# POW.net
KiCad netlist of a schematic drawn in Altium Designer
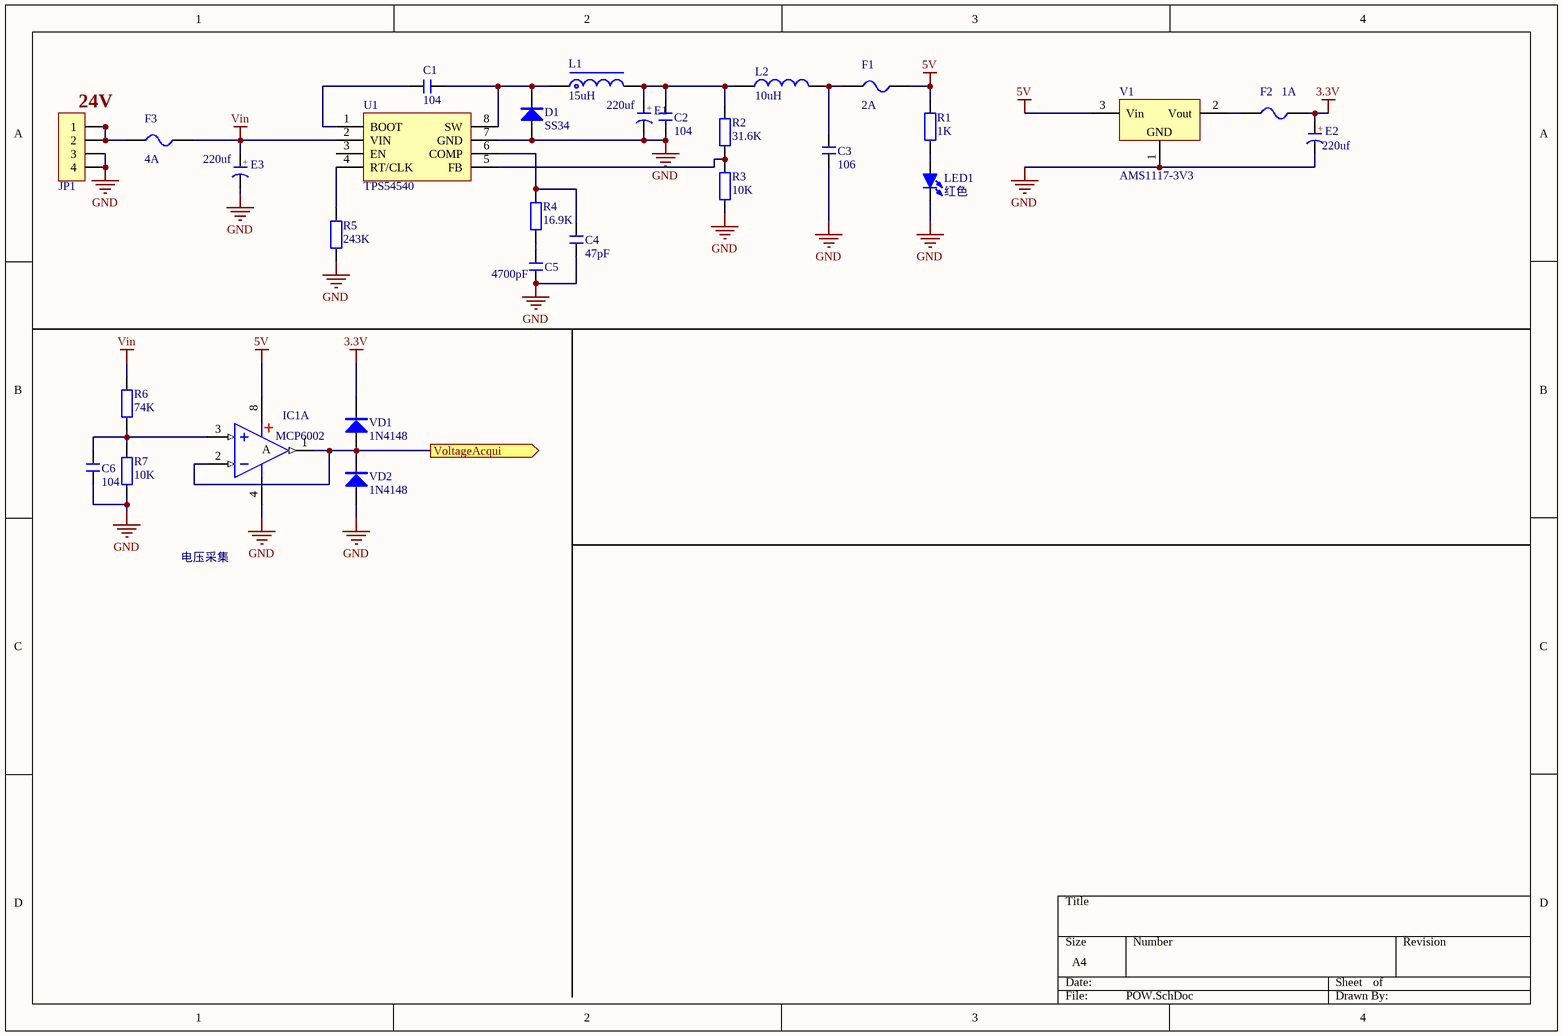
[diagram p0: POW.SchDoc]

(export (version "E")
  (design (tool "Eeschema 10.0.6"))
  (components
    (comp (ref "C1")
      (value "104")
      (footprint "C 0603_L")
      (description "无极性贴片电容")
      (fields (field (name "版权归属") "源创客"))
      (libsource (lib "3.1   - 电阻-电容-电感") (part "C"))
    )
    (comp (ref "C2")
      (value "104")
      (footprint "C 0603_L")
      (description "无极性贴片电容")
      (fields (field (name "版权归属") "源创客"))
      (libsource (lib "3.1   - 电阻-电容-电感") (part "C"))
    )
    (comp (ref "C3")
      (value "106")
      (footprint "C 0603_L")
      (description "无极性贴片电容")
      (fields (field (name "版权归属") "源创客"))
      (libsource (lib "3.1   - 电阻-电容-电感") (part "C"))
    )
    (comp (ref "C4")
      (value "47pF")
      (footprint "C 0603_L")
      (description "无极性贴片电容")
      (fields (field (name "版权归属") "源创客"))
      (libsource (lib "3.1   - 电阻-电容-电感") (part "C"))
    )
    (comp (ref "C5")
      (value "4700pF")
      (footprint "C 0603_L")
      (description "无极性贴片电容")
      (fields (field (name "版权归属") "源创客"))
      (libsource (lib "3.1   - 电阻-电容-电感") (part "C"))
    )
    (comp (ref "C6")
      (value "104")
      (footprint "C 0603_m")
      (description "无极性贴片电容")
      (fields (field (name "版权归属") "源创客"))
      (libsource (lib "电阻-电容-电感") (part "C"))
    )
    (comp (ref "D1")
      (value "SS34")
      (footprint "SMC")
      (description "肖特基二极管")
      (fields (field (name "版权归属") "源创客"))
      (libsource (lib "8.1   - 二极管-整流桥") (part "SS34"))
    )
    (comp (ref "E1")
      (value "220uf")
      (footprint "CM E(8*10.2)")
      (description "贴片电解电容")
      (fields (field (name "版权归属") "源创客"))
      (libsource (lib "电阻-电容-电感") (part "C-CM"))
    )
    (comp (ref "E2")
      (value "220uf")
      (footprint "CM E(8*10.2)")
      (description "贴片电解电容")
      (fields (field (name "版权归属") "源创客"))
      (libsource (lib "电阻-电容-电感") (part "C-CM"))
    )
    (comp (ref "E3")
      (value "220uf")
      (footprint "CM E(8*10.2)")
      (description "贴片电解电容")
      (fields (field (name "版权归属") "源创客"))
      (libsource (lib "电阻-电容-电感") (part "C-CM"))
    )
    (comp (ref "F1")
      (value "2A")
      (footprint "FU 1206")
      (description "贴片保险丝")
      (fields (field (name "版权归属") "源创客"))
      (libsource (lib "保险丝-晶振") (part "FU"))
    )
    (comp (ref "F2")
      (value "1A")
      (footprint "FU 0805")
      (description "贴片保险丝")
      (fields (field (name "版权归属") "源创客"))
      (libsource (lib "保险丝-晶振") (part "FU"))
    )
    (comp (ref "F3")
      (value "4A")
      (footprint "FU 1206")
      (description "贴片保险丝")
      (fields (field (name "版权归属") "源创客"))
      (libsource (lib "保险丝-晶振") (part "FU"))
    )
    (comp (ref "IC1")
      (value "MCP6002")
      (footprint "SOP8_N")
      (description "双路运放")
      (fields (field (name "版权归属") "源创客"))
      (libsource (lib "IC芯片") (part "LM358"))
    )
    (comp (ref "JP1")
      (value "HDR-1X4")
      (footprint "XH2.54-LI-4P")
      (description "4P接插件")
      (fields (field (name "版权归属") "源创客"))
      (libsource (lib "4.5   - 接插件-脚距2.54") (part "Header 4"))
    )
    (comp (ref "L1")
      (value "15uH")
      (footprint "CDRH73")
      (description "功率屏蔽电感")
      (fields (field (name "版权归属") "源创客"))
      (libsource (lib "电阻-电容-电感") (part "L-CDRH"))
    )
    (comp (ref "L2")
      (value "10uH")
      (footprint "L 0805")
      (description "小功率贴片电感")
      (fields (field (name "版权归属") "源创客"))
      (libsource (lib "电阻-电容-电感") (part "L"))
    )
    (comp (ref "LED1")
      (value "红色")
      (footprint "LED 0603G")
      (description "贴片LED")
      (fields (field (name "版权归属") "源创客"))
      (libsource (lib "LED") (part "LED-SMD"))
    )
    (comp (ref "R1")
      (value "1K")
      (footprint "R 0603_L")
      (description "贴片电阻")
      (fields (field (name "版权归属") "源创客"))
      (libsource (lib "3.1   - 电阻-电容-电感") (part "R"))
    )
    (comp (ref "R2")
      (value "31.6K")
      (footprint "R 0603_L")
      (description "贴片电阻")
      (fields (field (name "版权归属") "源创客"))
      (libsource (lib "3.1   - 电阻-电容-电感") (part "R"))
    )
    (comp (ref "R3")
      (value "10K")
      (footprint "R 0603_L")
      (description "贴片电阻")
      (fields (field (name "版权归属") "源创客"))
      (libsource (lib "3.1   - 电阻-电容-电感") (part "R"))
    )
    (comp (ref "R4")
      (value "16.9K")
      (footprint "R 0603_L")
      (description "贴片电阻")
      (fields (field (name "版权归属") "源创客"))
      (libsource (lib "3.1   - 电阻-电容-电感") (part "R"))
    )
    (comp (ref "R5")
      (value "243K")
      (footprint "R 0603_L")
      (description "贴片电阻")
      (fields (field (name "版权归属") "源创客"))
      (libsource (lib "3.1   - 电阻-电容-电感") (part "R"))
    )
    (comp (ref "R6")
      (value "74K")
      (footprint "R 0603_L")
      (description "贴片电阻")
      (fields (field (name "版权归属") "源创客"))
      (libsource (lib "3.1   - 电阻-电容-电感") (part "R"))
    )
    (comp (ref "R7")
      (value "10K")
      (footprint "R 0603_L")
      (description "贴片电阻")
      (fields (field (name "版权归属") "源创客"))
      (libsource (lib "3.1   - 电阻-电容-电感") (part "R"))
    )
    (comp (ref "U1")
      (value "TPS54540")
      (footprint "自编封装库:SOP8_1")
      (libsource (lib "自编原件库") (part "TPS54540"))
    )
    (comp (ref "V1")
      (value "AMS1117-3V3")
      (footprint "SOT223_M")
      (description "三端稳压芯片")
      (fields (field (name "版权归属") "源创客"))
      (libsource (lib "IC芯片") (part "AMS1117"))
    )
    (comp (ref "VD1")
      (value "1N4148")
      (footprint "SOD-323")
      (description "高速开关二极管")
      (fields (field (name "版权归属") "源创客"))
      (libsource (lib "二极管-整流桥") (part "1N4148"))
    )
    (comp (ref "VD2")
      (value "1N4148")
      (footprint "SOD-323")
      (description "高速开关二极管")
      (fields (field (name "版权归属") "源创客"))
      (libsource (lib "二极管-整流桥") (part "1N4148"))
    )
  )
  (nets
    (net (code "1") (name "/VoltageAcqui") (class "Default")
      (node (ref "IC1") (pin "1") (pinfunction "OUT_1") (pintype "output"))
      (node (ref "IC1") (pin "2") (pinfunction "IN-_2") (pintype "input"))
      (node (ref "VD1") (pin "1") (pinfunction "A_1") (pintype "passive"))
      (node (ref "VD2") (pin "2") (pinfunction "K_2") (pintype "passive"))
    )
    (net (code "2") (name "3.3V") (class "Default")
      (node (ref "E2") (pin "1") (pinfunction "A_1") (pintype "passive"))
      (node (ref "F2") (pin "2") (pinfunction "2_2") (pintype "passive"))
      (node (ref "VD1") (pin "2") (pinfunction "K_2") (pintype "passive"))
    )
    (net (code "3") (name "5V") (class "Default")
      (node (ref "F1") (pin "2") (pinfunction "2_2") (pintype "passive"))
      (node (ref "IC1") (pin "8") (pinfunction "V+_8") (pintype "power_in"))
      (node (ref "R1") (pin "2") (pinfunction "2_2") (pintype "passive"))
      (node (ref "V1") (pin "3") (pinfunction "Vin_3") (pintype "passive"))
    )
    (net (code "4") (name "GND") (class "Default")
      (node (ref "C2") (pin "1") (pinfunction "1_1") (pintype "passive"))
      (node (ref "C3") (pin "1") (pinfunction "1_1") (pintype "passive"))
      (node (ref "C4") (pin "1") (pinfunction "1_1") (pintype "passive"))
      (node (ref "C5") (pin "1") (pinfunction "1_1") (pintype "passive"))
      (node (ref "C6") (pin "1") (pinfunction "1_1") (pintype "passive"))
      (node (ref "D1") (pin "1") (pinfunction "A_1") (pintype "passive"))
      (node (ref "E1") (pin "2") (pinfunction "K_2") (pintype "passive"))
      (node (ref "E2") (pin "2") (pinfunction "K_2") (pintype "passive"))
      (node (ref "E3") (pin "2") (pinfunction "K_2") (pintype "passive"))
      (node (ref "IC1") (pin "4") (pinfunction "V-_4") (pintype "power_in"))
      (node (ref "JP1") (pin "3") (pinfunction "3_3") (pintype "passive"))
      (node (ref "JP1") (pin "4") (pinfunction "4_4") (pintype "passive"))
      (node (ref "LED1") (pin "2") (pinfunction "K_2") (pintype "passive"))
      (node (ref "R3") (pin "1") (pinfunction "1_1") (pintype "passive"))
      (node (ref "R5") (pin "1") (pinfunction "1_1") (pintype "passive"))
      (node (ref "R7") (pin "1") (pinfunction "1_1") (pintype "passive"))
      (node (ref "U1") (pin "7") (pinfunction "GND_7") (pintype "passive"))
      (node (ref "V1") (pin "1") (pinfunction "GND_1") (pintype "passive"))
      (node (ref "VD2") (pin "1") (pinfunction "A_1") (pintype "passive"))
    )
    (net (code "5") (name "Net-(C3-Pad2)") (class "Default")
      (node (ref "C3") (pin "2") (pinfunction "2_2") (pintype "passive"))
      (node (ref "F1") (pin "1") (pinfunction "1_1") (pintype "passive"))
      (node (ref "L2") (pin "2") (pinfunction "2_2") (pintype "passive"))
    )
    (net (code "6") (name "Net-(C5-Pad2)") (class "Default")
      (node (ref "C5") (pin "2") (pinfunction "2_2") (pintype "passive"))
      (node (ref "R4") (pin "1") (pinfunction "1_1") (pintype "passive"))
    )
    (net (code "7") (name "Net-(D1-K)") (class "Default")
      (node (ref "C1") (pin "2") (pinfunction "2_2") (pintype "passive"))
      (node (ref "D1") (pin "2") (pinfunction "K_2") (pintype "passive"))
      (node (ref "L1") (pin "1") (pinfunction "1_1") (pintype "passive"))
      (node (ref "U1") (pin "8") (pinfunction "SW_8") (pintype "passive"))
    )
    (net (code "8") (name "Net-(E1-A)") (class "Default")
      (node (ref "C2") (pin "2") (pinfunction "2_2") (pintype "passive"))
      (node (ref "E1") (pin "1") (pinfunction "A_1") (pintype "passive"))
      (node (ref "L1") (pin "2") (pinfunction "2_2") (pintype "passive"))
      (node (ref "L2") (pin "1") (pinfunction "1_1") (pintype "passive"))
      (node (ref "R2") (pin "2") (pinfunction "2_2") (pintype "passive"))
    )
    (net (code "9") (name "Net-(F3-Pad1)") (class "Default")
      (node (ref "F3") (pin "1") (pinfunction "1_1") (pintype "passive"))
      (node (ref "JP1") (pin "1") (pinfunction "1_1") (pintype "passive"))
      (node (ref "JP1") (pin "2") (pinfunction "2_2") (pintype "passive"))
    )
    (net (code "10") (name "Net-(IC1A-IN+)") (class "Default")
      (node (ref "C6") (pin "2") (pinfunction "2_2") (pintype "passive"))
      (node (ref "IC1") (pin "3") (pinfunction "IN+_3") (pintype "input"))
      (node (ref "R6") (pin "1") (pinfunction "1_1") (pintype "passive"))
      (node (ref "R7") (pin "2") (pinfunction "2_2") (pintype "passive"))
    )
    (net (code "11") (name "Net-(LED1-A)") (class "Default")
      (node (ref "LED1") (pin "1") (pinfunction "A_1") (pintype "passive"))
      (node (ref "R1") (pin "1") (pinfunction "1_1") (pintype "passive"))
    )
    (net (code "12") (name "Net-(U1-BOOT)") (class "Default")
      (node (ref "C1") (pin "1") (pinfunction "1_1") (pintype "passive"))
      (node (ref "U1") (pin "1") (pinfunction "BOOT_1") (pintype "passive"))
    )
    (net (code "13") (name "Net-(U1-COMP)") (class "Default")
      (node (ref "C4") (pin "2") (pinfunction "2_2") (pintype "passive"))
      (node (ref "R4") (pin "2") (pinfunction "2_2") (pintype "passive"))
      (node (ref "U1") (pin "6") (pinfunction "COMP_6") (pintype "passive"))
    )
    (net (code "14") (name "Net-(U1-FB)") (class "Default")
      (node (ref "R2") (pin "1") (pinfunction "1_1") (pintype "passive"))
      (node (ref "R3") (pin "2") (pinfunction "2_2") (pintype "passive"))
      (node (ref "U1") (pin "5") (pinfunction "FB_5") (pintype "passive"))
    )
    (net (code "15") (name "Net-(U1-RT{slash}CLK)") (class "Default")
      (node (ref "R5") (pin "2") (pinfunction "2_2") (pintype "passive"))
      (node (ref "U1") (pin "4") (pinfunction "RT/CLK_4") (pintype "passive"))
    )
    (net (code "16") (name "Net-(V1-Vout)") (class "Default")
      (node (ref "F2") (pin "1") (pinfunction "1_1") (pintype "passive"))
      (node (ref "V1") (pin "2") (pinfunction "Vout_2") (pintype "passive"))
    )
    (net (code "17") (name "Vin") (class "Default")
      (node (ref "E3") (pin "1") (pinfunction "A_1") (pintype "passive"))
      (node (ref "F3") (pin "2") (pinfunction "2_2") (pintype "passive"))
      (node (ref "R6") (pin "2") (pinfunction "2_2") (pintype "passive"))
      (node (ref "U1") (pin "2") (pinfunction "VIN_2") (pintype "passive"))
    )
    (net (code "18") (name "unconnected-(U1-EN-Pad3)") (class "Default")
      (node (ref "U1") (pin "3") (pinfunction "EN_3") (pintype "passive"))
    )
  )
)
